# design.net
KiCad netlist of a schematic drawn in EasyEDA Pro
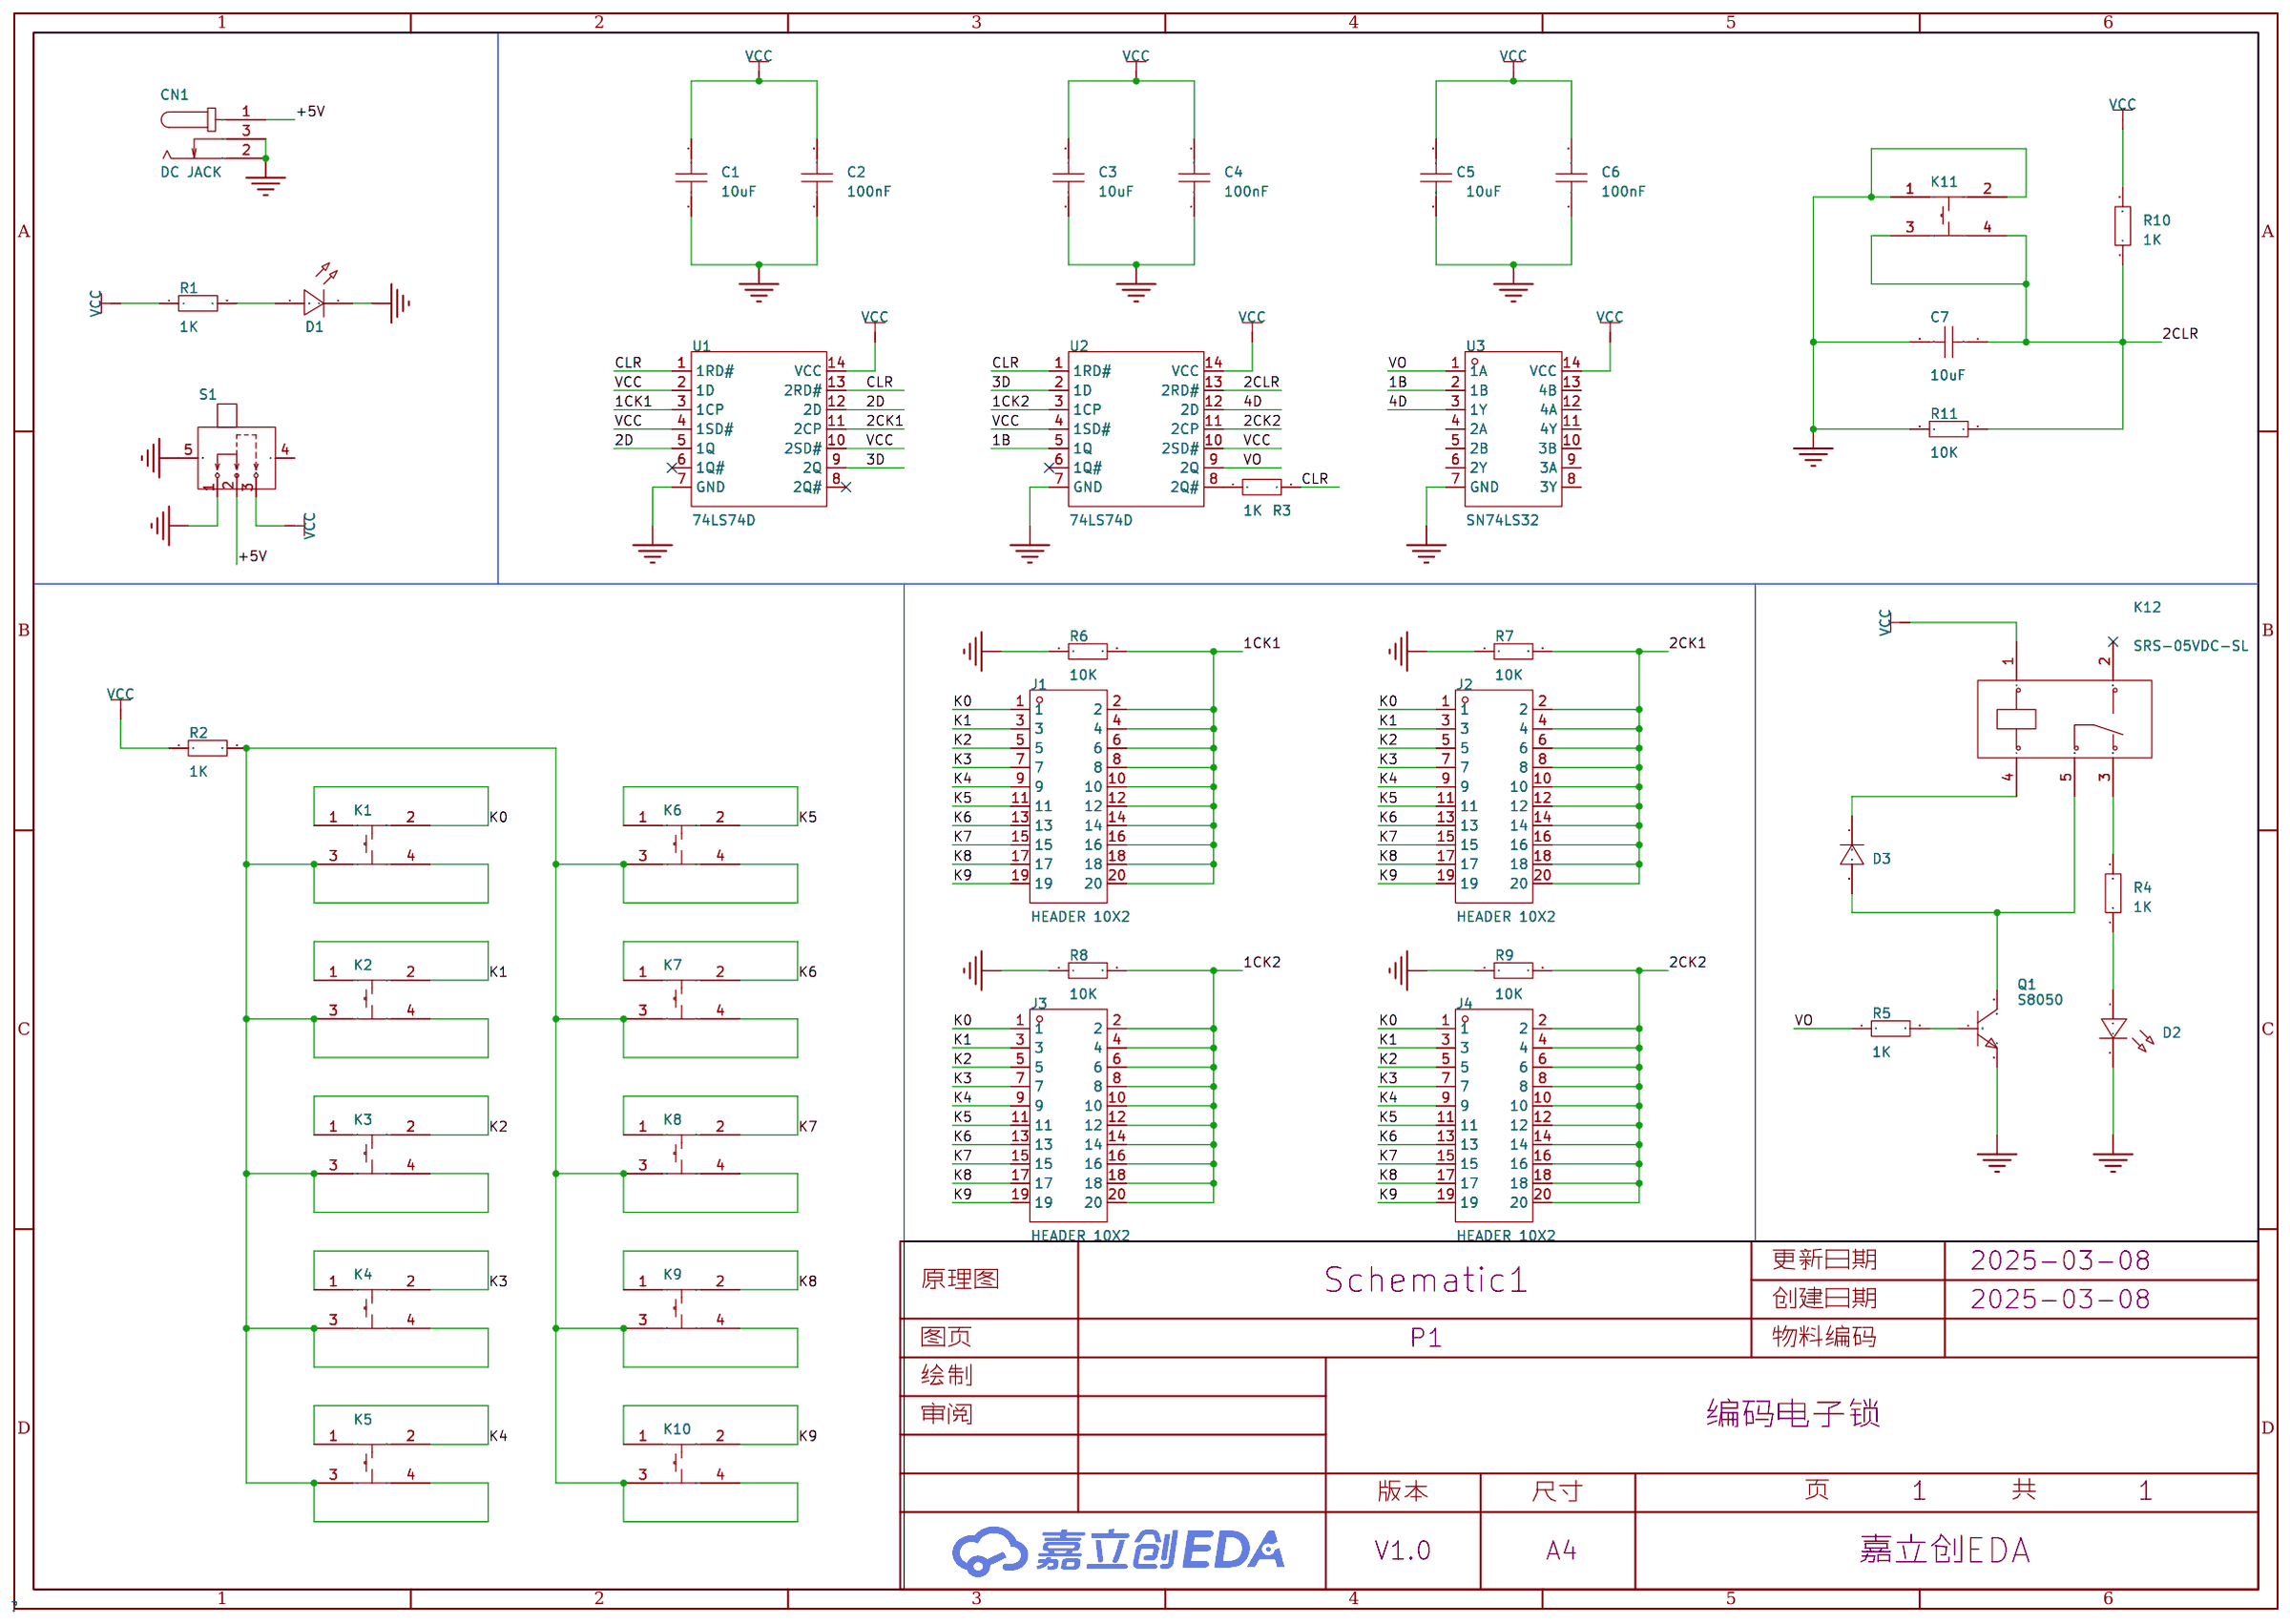
[diagram p0: schematic sheet]

(export (version "E")
  (design (tool "Eeschema 10.0.6"))
  (components
    (comp (ref "C1")
      (value "10uF")
      (footprint "easyedapro:C0805")
      (libsource (lib "easyedapro") (part "CapAcitance"))
    )
    (comp (ref "C2")
      (value "100nF")
      (footprint "easyedapro:C0805")
      (libsource (lib "easyedapro") (part "CapAcitance"))
    )
    (comp (ref "C3")
      (value "10uF")
      (footprint "easyedapro:C0805")
      (libsource (lib "easyedapro") (part "CapAcitance"))
    )
    (comp (ref "C4")
      (value "100nF")
      (footprint "easyedapro:C0805")
      (libsource (lib "easyedapro") (part "CapAcitance"))
    )
    (comp (ref "C5")
      (value "10uF")
      (footprint "easyedapro:C0805")
      (libsource (lib "easyedapro") (part "CapAcitance"))
    )
    (comp (ref "C6")
      (value "100nF")
      (footprint "easyedapro:C0805")
      (libsource (lib "easyedapro") (part "CapAcitance"))
    )
    (comp (ref "C7")
      (value "10uF")
      (footprint "easyedapro:C0805")
      (libsource (lib "easyedapro") (part "CapAcitance"))
    )
    (comp (ref "CN1")
      (value "DC JACK")
      (footprint "easyedapro:DC-IN-TH_DC005")
      (description "连接器类型:DC电源插座;安装方式:弯插;触点内径:2mm;触点外径:6.3mm;额定电流:500mA;额定电压:30V;工作温度范围:-25°C~+70°C;")
      (fields (field (name "Manufacturer") "SHOU HAN(首韩)"))
      (libsource (lib "easyedapro") (part "DC005_C431533"))
    )
    (comp (ref "D1")
      (value "~")
      (footprint "easyedapro:LED_TH-3mm")
      (libsource (lib "easyedapro") (part "LED_TH-R"))
    )
    (comp (ref "D2")
      (value "~")
      (footprint "easyedapro:LED_TH-3mm")
      (libsource (lib "easyedapro") (part "LED_TH-R"))
    )
    (comp (ref "D3")
      (value "LL4148-GS08")
      (footprint "easyedapro:SOD-80_L3.5-W1.5-RD")
      (description "二极管配置:-;正向压降(Vf):860mV@50mA;直流反向耐压(Vr):75V;平均整流电流(Io):300mA;功率:500mW;反向恢复时间(trr):8ns;")
      (fields (field (name "Manufacturer") "VISHAY(威世)"))
      (libsource (lib "easyedapro") (part "LL4148-GS08"))
    )
    (comp (ref "J1")
      (value "HEADER 10X2")
      (footprint "easyedapro:HDR-TH_20P-P2.54-V-M-R2-C10-S2.54")
      (description "插针结构:2x10P;间距:2.54mm;排数:双排;总PIN位数:20P;")
      (fields (field (name "Manufacturer") "ZHOURI(洲日)"))
      (libsource (lib "easyedapro") (part "2.54-2*10"))
    )
    (comp (ref "J2")
      (value "HEADER 10X2")
      (footprint "easyedapro:HDR-TH_20P-P2.54-V-M-R2-C10-S2.54")
      (description "插针结构:2x10P;间距:2.54mm;排数:双排;总PIN位数:20P;")
      (fields (field (name "Manufacturer") "ZHOURI(洲日)"))
      (libsource (lib "easyedapro") (part "2.54-2*10"))
    )
    (comp (ref "J3")
      (value "HEADER 10X2")
      (footprint "easyedapro:HDR-TH_20P-P2.54-V-M-R2-C10-S2.54")
      (description "插针结构:2x10P;间距:2.54mm;排数:双排;总PIN位数:20P;")
      (fields (field (name "Manufacturer") "ZHOURI(洲日)"))
      (libsource (lib "easyedapro") (part "2.54-2*10"))
    )
    (comp (ref "J4")
      (value "HEADER 10X2")
      (footprint "easyedapro:HDR-TH_20P-P2.54-V-M-R2-C10-S2.54")
      (description "插针结构:2x10P;间距:2.54mm;排数:双排;总PIN位数:20P;")
      (fields (field (name "Manufacturer") "ZHOURI(洲日)"))
      (libsource (lib "easyedapro") (part "2.54-2*10"))
    )
    (comp (ref "K1")
      (value "TS-1002S-04526C")
      (footprint "easyedapro:SW-SMD_4P-L6.0-W6.0-P4.50-LS9.0-2")
      (description "电路结构:单刀单掷;按钮形状:圆形按钮;安装方式:立贴;开关长度:6mm;开关宽度:6mm;开关高度:4.5mm;触点电流:50mA;额定电压(DC):12V;带灯:-;机械寿命:-;")
      (fields (field (name "Manufacturer") "XUNPU(讯普)"))
      (libsource (lib "easyedapro") (part "TS-1002S-04526C"))
    )
    (comp (ref "K2")
      (value "TS-1002S-04526C")
      (footprint "easyedapro:SW-SMD_4P-L6.0-W6.0-P4.50-LS9.0-2")
      (description "电路结构:单刀单掷;按钮形状:圆形按钮;安装方式:立贴;开关长度:6mm;开关宽度:6mm;开关高度:4.5mm;触点电流:50mA;额定电压(DC):12V;带灯:-;机械寿命:-;")
      (fields (field (name "Manufacturer") "XUNPU(讯普)"))
      (libsource (lib "easyedapro") (part "TS-1002S-04526C"))
    )
    (comp (ref "K3")
      (value "TS-1002S-04526C")
      (footprint "easyedapro:SW-SMD_4P-L6.0-W6.0-P4.50-LS9.0-2")
      (description "电路结构:单刀单掷;按钮形状:圆形按钮;安装方式:立贴;开关长度:6mm;开关宽度:6mm;开关高度:4.5mm;触点电流:50mA;额定电压(DC):12V;带灯:-;机械寿命:-;")
      (fields (field (name "Manufacturer") "XUNPU(讯普)"))
      (libsource (lib "easyedapro") (part "TS-1002S-04526C"))
    )
    (comp (ref "K4")
      (value "TS-1002S-04526C")
      (footprint "easyedapro:SW-SMD_4P-L6.0-W6.0-P4.50-LS9.0-2")
      (description "电路结构:单刀单掷;按钮形状:圆形按钮;安装方式:立贴;开关长度:6mm;开关宽度:6mm;开关高度:4.5mm;触点电流:50mA;额定电压(DC):12V;带灯:-;机械寿命:-;")
      (fields (field (name "Manufacturer") "XUNPU(讯普)"))
      (libsource (lib "easyedapro") (part "TS-1002S-04526C"))
    )
    (comp (ref "K5")
      (value "TS-1002S-04526C")
      (footprint "easyedapro:SW-SMD_4P-L6.0-W6.0-P4.50-LS9.0-2")
      (description "电路结构:单刀单掷;按钮形状:圆形按钮;安装方式:立贴;开关长度:6mm;开关宽度:6mm;开关高度:4.5mm;触点电流:50mA;额定电压(DC):12V;带灯:-;机械寿命:-;")
      (fields (field (name "Manufacturer") "XUNPU(讯普)"))
      (libsource (lib "easyedapro") (part "TS-1002S-04526C"))
    )
    (comp (ref "K6")
      (value "TS-1002S-04526C")
      (footprint "easyedapro:SW-SMD_4P-L6.0-W6.0-P4.50-LS9.0-2")
      (description "电路结构:单刀单掷;按钮形状:圆形按钮;安装方式:立贴;开关长度:6mm;开关宽度:6mm;开关高度:4.5mm;触点电流:50mA;额定电压(DC):12V;带灯:-;机械寿命:-;")
      (fields (field (name "Manufacturer") "XUNPU(讯普)"))
      (libsource (lib "easyedapro") (part "TS-1002S-04526C"))
    )
    (comp (ref "K7")
      (value "TS-1002S-04526C")
      (footprint "easyedapro:SW-SMD_4P-L6.0-W6.0-P4.50-LS9.0-2")
      (description "电路结构:单刀单掷;按钮形状:圆形按钮;安装方式:立贴;开关长度:6mm;开关宽度:6mm;开关高度:4.5mm;触点电流:50mA;额定电压(DC):12V;带灯:-;机械寿命:-;")
      (fields (field (name "Manufacturer") "XUNPU(讯普)"))
      (libsource (lib "easyedapro") (part "TS-1002S-04526C"))
    )
    (comp (ref "K8")
      (value "TS-1002S-04526C")
      (footprint "easyedapro:SW-SMD_4P-L6.0-W6.0-P4.50-LS9.0-2")
      (description "电路结构:单刀单掷;按钮形状:圆形按钮;安装方式:立贴;开关长度:6mm;开关宽度:6mm;开关高度:4.5mm;触点电流:50mA;额定电压(DC):12V;带灯:-;机械寿命:-;")
      (fields (field (name "Manufacturer") "XUNPU(讯普)"))
      (libsource (lib "easyedapro") (part "TS-1002S-04526C"))
    )
    (comp (ref "K9")
      (value "TS-1002S-04526C")
      (footprint "easyedapro:SW-SMD_4P-L6.0-W6.0-P4.50-LS9.0-2")
      (description "电路结构:单刀单掷;按钮形状:圆形按钮;安装方式:立贴;开关长度:6mm;开关宽度:6mm;开关高度:4.5mm;触点电流:50mA;额定电压(DC):12V;带灯:-;机械寿命:-;")
      (fields (field (name "Manufacturer") "XUNPU(讯普)"))
      (libsource (lib "easyedapro") (part "TS-1002S-04526C"))
    )
    (comp (ref "K10")
      (value "TS-1002S-04526C")
      (footprint "easyedapro:SW-SMD_4P-L6.0-W6.0-P4.50-LS9.0-2")
      (description "电路结构:单刀单掷;按钮形状:圆形按钮;安装方式:立贴;开关长度:6mm;开关宽度:6mm;开关高度:4.5mm;触点电流:50mA;额定电压(DC):12V;带灯:-;机械寿命:-;")
      (fields (field (name "Manufacturer") "XUNPU(讯普)"))
      (libsource (lib "easyedapro") (part "TS-1002S-04526C"))
    )
    (comp (ref "K11")
      (value "TS-1002S-04526C")
      (footprint "easyedapro:SW-SMD_4P-L6.0-W6.0-P4.50-LS9.0-2")
      (description "电路结构:单刀单掷;按钮形状:圆形按钮;安装方式:立贴;开关长度:6mm;开关宽度:6mm;开关高度:4.5mm;触点电流:50mA;额定电压(DC):12V;带灯:-;机械寿命:-;")
      (fields (field (name "Manufacturer") "XUNPU(讯普)"))
      (libsource (lib "easyedapro") (part "TS-1002S-04526C"))
    )
    (comp (ref "K12")
      (value "SRS-05VDC-SL")
      (footprint "easyedapro:RELAY-TH_SRD-XXVDC-XL-C")
      (description "线圈电压:5V;触点形式:一组转换:1C(单刀双掷-转换);触点容量(电阻负载):-;最大切换电压:250V@AC;最大切换电流:15A;")
      (fields (field (name "Manufacturer") "松乐"))
      (libsource (lib "easyedapro") (part "SRD-05VDC-SL-C"))
    )
    (comp (ref "Q1")
      (value "S8050")
      (footprint "easyedapro:SOT-23-3_L3.0-W1.7-P0.95-LS2.9-BR")
      (description "晶体管类型:NPN;集电极电流(Ic):500mA;集射极击穿电压(Vceo):25V;耗散功率(Pd):300mW;直流电流增益(hFE):120@500mA,1V;")
      (fields (field (name "Manufacturer") "MDD(辰达半导体)"))
      (libsource (lib "easyedapro") (part "S8050-J3Y"))
    )
    (comp (ref "R1") (value "1K") (footprint "easyedapro:R0805") (libsource (lib "easyedapro") (part "电阻")))
    (comp (ref "R2") (value "1K") (footprint "easyedapro:R0805") (libsource (lib "easyedapro") (part "电阻")))
    (comp (ref "R3") (value "1K") (footprint "easyedapro:R0805") (libsource (lib "easyedapro") (part "电阻")))
    (comp (ref "R4") (value "1K") (footprint "easyedapro:R0805") (libsource (lib "easyedapro") (part "电阻")))
    (comp (ref "R5") (value "1K") (footprint "easyedapro:R0805") (libsource (lib "easyedapro") (part "电阻")))
    (comp (ref "R6") (value "10K") (footprint "easyedapro:R0805") (libsource (lib "easyedapro") (part "电阻")))
    (comp (ref "R7") (value "10K") (footprint "easyedapro:R0805") (libsource (lib "easyedapro") (part "电阻")))
    (comp (ref "R8") (value "10K") (footprint "easyedapro:R0805") (libsource (lib "easyedapro") (part "电阻")))
    (comp (ref "R9") (value "10K") (footprint "easyedapro:R0805") (libsource (lib "easyedapro") (part "电阻")))
    (comp (ref "R10") (value "1K") (footprint "easyedapro:R0805") (libsource (lib "easyedapro") (part "电阻")))
    (comp (ref "R11") (value "10K") (footprint "easyedapro:R0805") (libsource (lib "easyedapro") (part "电阻")))
    (comp (ref "S1")
      (value "SS12F44G5")
      (footprint "easyedapro:SW-TH_SHOU-HAN_SS12F44G4")
      (description "拨动开关 立式直脚插件 二档 柄高5mm")
      (fields (field (name "Manufacturer") "HanElectricity(瀚源)"))
      (libsource (lib "easyedapro") (part "SS12F44G5"))
    )
    (comp (ref "U1")
      (value "74LS74D")
      (footprint "easyedapro:DIP-14_L19.1-W6.4-P2.54-LS7.6-BL")
      (description "类型:D-型;工作电压:2V~6V;时钟频率(fc):82MHz;元件数:2;每个元件位数:1;静态电流(Iq):40uA;")
      (fields (field (name "Manufacturer") "LX(灵星芯微)"))
      (libsource (lib "easyedapro") (part "SN74LS74N"))
    )
    (comp (ref "U2")
      (value "74LS74D")
      (footprint "easyedapro:DIP-14_L19.1-W6.4-P2.54-LS7.6-BL")
      (description "类型:D-型;工作电压:2V~6V;时钟频率(fc):82MHz;元件数:2;每个元件位数:1;静态电流(Iq):40uA;")
      (fields (field (name "Manufacturer") "LX(灵星芯微)"))
      (libsource (lib "easyedapro") (part "SN74LS74N"))
    )
    (comp (ref "U3")
      (value "SN74LS32")
      (footprint "easyedapro:PDIP-14_L19.6-W6.5-P2.54-LS7.9-BL")
      (description "逻辑类型:或门;通道数:4;电源电压:4.75V~5.25V;最大传播延迟:22ns@5V,15pF;")
      (fields (field (name "Manufacturer") "TI(德州仪器)"))
      (libsource (lib "easyedapro") (part "SN74LS32N"))
    )
  )
  (nets
    (net (code "1") (name "/+5V") (class "Default")
      (node (ref "CN1") (pin "1") (pinfunction "1_1") (pintype "unspecified"))
      (node (ref "S1") (pin "2") (pinfunction "2_2") (pintype "unspecified"))
    )
    (net (code "2") (name "/1B") (class "Default")
      (node (ref "U2") (pin "5") (pinfunction "1Q_5") (pintype "unspecified"))
      (node (ref "U3") (pin "2") (pinfunction "1B_2") (pintype "unspecified"))
    )
    (net (code "3") (name "/1CK1") (class "Default")
      (node (ref "J1") (pin "10") (pinfunction "10_10") (pintype "unspecified"))
      (node (ref "J1") (pin "12") (pinfunction "12_12") (pintype "unspecified"))
      (node (ref "J1") (pin "14") (pinfunction "14_14") (pintype "unspecified"))
      (node (ref "J1") (pin "16") (pinfunction "16_16") (pintype "unspecified"))
      (node (ref "J1") (pin "18") (pinfunction "18_18") (pintype "unspecified"))
      (node (ref "J1") (pin "2") (pinfunction "2_2") (pintype "unspecified"))
      (node (ref "J1") (pin "20") (pinfunction "20_20") (pintype "unspecified"))
      (node (ref "J1") (pin "4") (pinfunction "4_4") (pintype "unspecified"))
      (node (ref "J1") (pin "6") (pinfunction "6_6") (pintype "unspecified"))
      (node (ref "J1") (pin "8") (pinfunction "8_8") (pintype "unspecified"))
      (node (ref "R6") (pin "2") (pinfunction "2_2") (pintype "input"))
      (node (ref "U1") (pin "3") (pinfunction "1CP_3") (pintype "unspecified"))
    )
    (net (code "4") (name "/1CK2") (class "Default")
      (node (ref "J3") (pin "10") (pinfunction "10_10") (pintype "unspecified"))
      (node (ref "J3") (pin "12") (pinfunction "12_12") (pintype "unspecified"))
      (node (ref "J3") (pin "14") (pinfunction "14_14") (pintype "unspecified"))
      (node (ref "J3") (pin "16") (pinfunction "16_16") (pintype "unspecified"))
      (node (ref "J3") (pin "18") (pinfunction "18_18") (pintype "unspecified"))
      (node (ref "J3") (pin "2") (pinfunction "2_2") (pintype "unspecified"))
      (node (ref "J3") (pin "20") (pinfunction "20_20") (pintype "unspecified"))
      (node (ref "J3") (pin "4") (pinfunction "4_4") (pintype "unspecified"))
      (node (ref "J3") (pin "6") (pinfunction "6_6") (pintype "unspecified"))
      (node (ref "J3") (pin "8") (pinfunction "8_8") (pintype "unspecified"))
      (node (ref "R8") (pin "2") (pinfunction "2_2") (pintype "input"))
      (node (ref "U2") (pin "3") (pinfunction "1CP_3") (pintype "unspecified"))
    )
    (net (code "5") (name "/2CK1") (class "Default")
      (node (ref "J2") (pin "10") (pinfunction "10_10") (pintype "unspecified"))
      (node (ref "J2") (pin "12") (pinfunction "12_12") (pintype "unspecified"))
      (node (ref "J2") (pin "14") (pinfunction "14_14") (pintype "unspecified"))
      (node (ref "J2") (pin "16") (pinfunction "16_16") (pintype "unspecified"))
      (node (ref "J2") (pin "18") (pinfunction "18_18") (pintype "unspecified"))
      (node (ref "J2") (pin "2") (pinfunction "2_2") (pintype "unspecified"))
      (node (ref "J2") (pin "20") (pinfunction "20_20") (pintype "unspecified"))
      (node (ref "J2") (pin "4") (pinfunction "4_4") (pintype "unspecified"))
      (node (ref "J2") (pin "6") (pinfunction "6_6") (pintype "unspecified"))
      (node (ref "J2") (pin "8") (pinfunction "8_8") (pintype "unspecified"))
      (node (ref "R7") (pin "2") (pinfunction "2_2") (pintype "input"))
      (node (ref "U1") (pin "11") (pinfunction "2CP_11") (pintype "unspecified"))
    )
    (net (code "6") (name "/2CK2") (class "Default")
      (node (ref "J4") (pin "10") (pinfunction "10_10") (pintype "unspecified"))
      (node (ref "J4") (pin "12") (pinfunction "12_12") (pintype "unspecified"))
      (node (ref "J4") (pin "14") (pinfunction "14_14") (pintype "unspecified"))
      (node (ref "J4") (pin "16") (pinfunction "16_16") (pintype "unspecified"))
      (node (ref "J4") (pin "18") (pinfunction "18_18") (pintype "unspecified"))
      (node (ref "J4") (pin "2") (pinfunction "2_2") (pintype "unspecified"))
      (node (ref "J4") (pin "20") (pinfunction "20_20") (pintype "unspecified"))
      (node (ref "J4") (pin "4") (pinfunction "4_4") (pintype "unspecified"))
      (node (ref "J4") (pin "6") (pinfunction "6_6") (pintype "unspecified"))
      (node (ref "J4") (pin "8") (pinfunction "8_8") (pintype "unspecified"))
      (node (ref "R9") (pin "2") (pinfunction "2_2") (pintype "input"))
      (node (ref "U2") (pin "11") (pinfunction "2CP_11") (pintype "unspecified"))
    )
    (net (code "7") (name "/2CLR") (class "Default")
      (node (ref "C7") (pin "1") (pinfunction "1_1") (pintype "input"))
      (node (ref "K11") (pin "3") (pinfunction "3_3") (pintype "unspecified"))
      (node (ref "K11") (pin "4") (pinfunction "4_4") (pintype "unspecified"))
      (node (ref "R10") (pin "1") (pinfunction "1_1") (pintype "input"))
      (node (ref "R11") (pin "1") (pinfunction "1_1") (pintype "input"))
      (node (ref "U2") (pin "13") (pinfunction "2RD#_13") (pintype "unspecified"))
    )
    (net (code "8") (name "/2D") (class "Default")
      (node (ref "U1") (pin "12") (pinfunction "2D_12") (pintype "unspecified"))
      (node (ref "U1") (pin "5") (pinfunction "1Q_5") (pintype "unspecified"))
    )
    (net (code "9") (name "/3D") (class "Default")
      (node (ref "U1") (pin "9") (pinfunction "2Q_9") (pintype "unspecified"))
      (node (ref "U2") (pin "2") (pinfunction "1D_2") (pintype "unspecified"))
    )
    (net (code "10") (name "/4D") (class "Default")
      (node (ref "U2") (pin "12") (pinfunction "2D_12") (pintype "unspecified"))
      (node (ref "U3") (pin "3") (pinfunction "1Y_3") (pintype "unspecified"))
    )
    (net (code "11") (name "/CLR") (class "Default")
      (node (ref "R3") (pin "2") (pinfunction "2_2") (pintype "input"))
      (node (ref "U1") (pin "1") (pinfunction "1RD#_1") (pintype "unspecified"))
      (node (ref "U1") (pin "13") (pinfunction "2RD#_13") (pintype "unspecified"))
      (node (ref "U2") (pin "1") (pinfunction "1RD#_1") (pintype "unspecified"))
    )
    (net (code "12") (name "/K0") (class "Default")
      (node (ref "J1") (pin "1") (pinfunction "1_1") (pintype "unspecified"))
      (node (ref "J2") (pin "1") (pinfunction "1_1") (pintype "unspecified"))
      (node (ref "J3") (pin "1") (pinfunction "1_1") (pintype "unspecified"))
      (node (ref "J4") (pin "1") (pinfunction "1_1") (pintype "unspecified"))
      (node (ref "K1") (pin "1") (pinfunction "1_1") (pintype "unspecified"))
      (node (ref "K1") (pin "2") (pinfunction "2_2") (pintype "unspecified"))
    )
    (net (code "13") (name "/K1") (class "Default")
      (node (ref "J1") (pin "3") (pinfunction "3_3") (pintype "unspecified"))
      (node (ref "J2") (pin "3") (pinfunction "3_3") (pintype "unspecified"))
      (node (ref "J3") (pin "3") (pinfunction "3_3") (pintype "unspecified"))
      (node (ref "J4") (pin "3") (pinfunction "3_3") (pintype "unspecified"))
      (node (ref "K2") (pin "1") (pinfunction "1_1") (pintype "unspecified"))
      (node (ref "K2") (pin "2") (pinfunction "2_2") (pintype "unspecified"))
    )
    (net (code "14") (name "/K2") (class "Default")
      (node (ref "J1") (pin "5") (pinfunction "5_5") (pintype "unspecified"))
      (node (ref "J2") (pin "5") (pinfunction "5_5") (pintype "unspecified"))
      (node (ref "J3") (pin "5") (pinfunction "5_5") (pintype "unspecified"))
      (node (ref "J4") (pin "5") (pinfunction "5_5") (pintype "unspecified"))
      (node (ref "K3") (pin "1") (pinfunction "1_1") (pintype "unspecified"))
      (node (ref "K3") (pin "2") (pinfunction "2_2") (pintype "unspecified"))
    )
    (net (code "15") (name "/K3") (class "Default")
      (node (ref "J1") (pin "7") (pinfunction "7_7") (pintype "unspecified"))
      (node (ref "J2") (pin "7") (pinfunction "7_7") (pintype "unspecified"))
      (node (ref "J3") (pin "7") (pinfunction "7_7") (pintype "unspecified"))
      (node (ref "J4") (pin "7") (pinfunction "7_7") (pintype "unspecified"))
      (node (ref "K4") (pin "1") (pinfunction "1_1") (pintype "unspecified"))
      (node (ref "K4") (pin "2") (pinfunction "2_2") (pintype "unspecified"))
    )
    (net (code "16") (name "/K4") (class "Default")
      (node (ref "J1") (pin "9") (pinfunction "9_9") (pintype "unspecified"))
      (node (ref "J2") (pin "9") (pinfunction "9_9") (pintype "unspecified"))
      (node (ref "J3") (pin "9") (pinfunction "9_9") (pintype "unspecified"))
      (node (ref "J4") (pin "9") (pinfunction "9_9") (pintype "unspecified"))
      (node (ref "K5") (pin "1") (pinfunction "1_1") (pintype "unspecified"))
      (node (ref "K5") (pin "2") (pinfunction "2_2") (pintype "unspecified"))
    )
    (net (code "17") (name "/K5") (class "Default")
      (node (ref "J1") (pin "11") (pinfunction "11_11") (pintype "unspecified"))
      (node (ref "J2") (pin "11") (pinfunction "11_11") (pintype "unspecified"))
      (node (ref "J3") (pin "11") (pinfunction "11_11") (pintype "unspecified"))
      (node (ref "J4") (pin "11") (pinfunction "11_11") (pintype "unspecified"))
      (node (ref "K6") (pin "1") (pinfunction "1_1") (pintype "unspecified"))
      (node (ref "K6") (pin "2") (pinfunction "2_2") (pintype "unspecified"))
    )
    (net (code "18") (name "/K6") (class "Default")
      (node (ref "J1") (pin "13") (pinfunction "13_13") (pintype "unspecified"))
      (node (ref "J2") (pin "13") (pinfunction "13_13") (pintype "unspecified"))
      (node (ref "J3") (pin "13") (pinfunction "13_13") (pintype "unspecified"))
      (node (ref "J4") (pin "13") (pinfunction "13_13") (pintype "unspecified"))
      (node (ref "K7") (pin "1") (pinfunction "1_1") (pintype "unspecified"))
      (node (ref "K7") (pin "2") (pinfunction "2_2") (pintype "unspecified"))
    )
    (net (code "19") (name "/K7") (class "Default")
      (node (ref "J1") (pin "15") (pinfunction "15_15") (pintype "unspecified"))
      (node (ref "J2") (pin "15") (pinfunction "15_15") (pintype "unspecified"))
      (node (ref "J3") (pin "15") (pinfunction "15_15") (pintype "unspecified"))
      (node (ref "J4") (pin "15") (pinfunction "15_15") (pintype "unspecified"))
      (node (ref "K8") (pin "1") (pinfunction "1_1") (pintype "unspecified"))
      (node (ref "K8") (pin "2") (pinfunction "2_2") (pintype "unspecified"))
    )
    (net (code "20") (name "/K8") (class "Default")
      (node (ref "J1") (pin "17") (pinfunction "17_17") (pintype "unspecified"))
      (node (ref "J2") (pin "17") (pinfunction "17_17") (pintype "unspecified"))
      (node (ref "J3") (pin "17") (pinfunction "17_17") (pintype "unspecified"))
      (node (ref "J4") (pin "17") (pinfunction "17_17") (pintype "unspecified"))
      (node (ref "K9") (pin "1") (pinfunction "1_1") (pintype "unspecified"))
      (node (ref "K9") (pin "2") (pinfunction "2_2") (pintype "unspecified"))
    )
    (net (code "21") (name "/K9") (class "Default")
      (node (ref "J1") (pin "19") (pinfunction "19_19") (pintype "unspecified"))
      (node (ref "J2") (pin "19") (pinfunction "19_19") (pintype "unspecified"))
      (node (ref "J3") (pin "19") (pinfunction "19_19") (pintype "unspecified"))
      (node (ref "J4") (pin "19") (pinfunction "19_19") (pintype "unspecified"))
      (node (ref "K10") (pin "1") (pinfunction "1_1") (pintype "unspecified"))
      (node (ref "K10") (pin "2") (pinfunction "2_2") (pintype "unspecified"))
    )
    (net (code "22") (name "/VO") (class "Default")
      (node (ref "R5") (pin "1") (pinfunction "1_1") (pintype "input"))
      (node (ref "U2") (pin "9") (pinfunction "2Q_9") (pintype "unspecified"))
      (node (ref "U3") (pin "1") (pinfunction "1A_1") (pintype "unspecified"))
    )
    (net (code "23") (name "GND") (class "Default")
      (node (ref "C1") (pin "1") (pinfunction "1_1") (pintype "input"))
      (node (ref "C2") (pin "1") (pinfunction "1_1") (pintype "input"))
      (node (ref "C3") (pin "1") (pinfunction "1_1") (pintype "input"))
      (node (ref "C4") (pin "1") (pinfunction "1_1") (pintype "input"))
      (node (ref "C5") (pin "1") (pinfunction "1_1") (pintype "input"))
      (node (ref "C6") (pin "1") (pinfunction "1_1") (pintype "input"))
      (node (ref "C7") (pin "2") (pinfunction "2_2") (pintype "input"))
      (node (ref "CN1") (pin "2") (pinfunction "2_2") (pintype "unspecified"))
      (node (ref "CN1") (pin "3") (pinfunction "3_3") (pintype "unspecified"))
      (node (ref "D1") (pin "2") (pinfunction "A_2") (pintype "input"))
      (node (ref "D2") (pin "2") (pinfunction "A_2") (pintype "input"))
      (node (ref "K11") (pin "1") (pinfunction "1_1") (pintype "unspecified"))
      (node (ref "K11") (pin "2") (pinfunction "2_2") (pintype "unspecified"))
      (node (ref "Q1") (pin "2") (pinfunction "E_2") (pintype "unspecified"))
      (node (ref "R11") (pin "2") (pinfunction "2_2") (pintype "input"))
      (node (ref "R6") (pin "1") (pinfunction "1_1") (pintype "input"))
      (node (ref "R7") (pin "1") (pinfunction "1_1") (pintype "input"))
      (node (ref "R8") (pin "1") (pinfunction "1_1") (pintype "input"))
      (node (ref "R9") (pin "1") (pinfunction "1_1") (pintype "input"))
      (node (ref "S1") (pin "1") (pinfunction "1_1") (pintype "unspecified"))
      (node (ref "S1") (pin "5") (pinfunction "5_5") (pintype "unspecified"))
      (node (ref "U1") (pin "7") (pinfunction "GND_7") (pintype "unspecified"))
      (node (ref "U2") (pin "7") (pinfunction "GND_7") (pintype "unspecified"))
      (node (ref "U3") (pin "7") (pinfunction "GND_7") (pintype "unspecified"))
    )
    (net (code "24") (name "Net-(D1-C)") (class "Default")
      (node (ref "D1") (pin "1") (pinfunction "C_1") (pintype "input"))
      (node (ref "R1") (pin "2") (pinfunction "2_2") (pintype "input"))
    )
    (net (code "25") (name "Net-(D2-C)") (class "Default")
      (node (ref "D2") (pin "1") (pinfunction "C_1") (pintype "input"))
      (node (ref "R4") (pin "1") (pinfunction "1_1") (pintype "input"))
    )
    (net (code "26") (name "Net-(D3-A)") (class "Default")
      (node (ref "D3") (pin "2") (pinfunction "A_2") (pintype "unspecified"))
      (node (ref "K12") (pin "5") (pinfunction "5_5") (pintype "input"))
      (node (ref "Q1") (pin "3") (pinfunction "C_3") (pintype "unspecified"))
    )
    (net (code "27") (name "Net-(D3-C)") (class "Default")
      (node (ref "D3") (pin "1") (pinfunction "C_1") (pintype "unspecified"))
      (node (ref "K12") (pin "4") (pinfunction "4_4") (pintype "input"))
    )
    (net (code "28") (name "Net-(K1-Pad3)") (class "Default")
      (node (ref "K1") (pin "3") (pinfunction "3_3") (pintype "unspecified"))
      (node (ref "K1") (pin "4") (pinfunction "4_4") (pintype "unspecified"))
      (node (ref "K10") (pin "3") (pinfunction "3_3") (pintype "unspecified"))
      (node (ref "K10") (pin "4") (pinfunction "4_4") (pintype "unspecified"))
      (node (ref "K2") (pin "3") (pinfunction "3_3") (pintype "unspecified"))
      (node (ref "K2") (pin "4") (pinfunction "4_4") (pintype "unspecified"))
      (node (ref "K3") (pin "3") (pinfunction "3_3") (pintype "unspecified"))
      (node (ref "K3") (pin "4") (pinfunction "4_4") (pintype "unspecified"))
      (node (ref "K4") (pin "3") (pinfunction "3_3") (pintype "unspecified"))
      (node (ref "K4") (pin "4") (pinfunction "4_4") (pintype "unspecified"))
      (node (ref "K5") (pin "3") (pinfunction "3_3") (pintype "unspecified"))
      (node (ref "K5") (pin "4") (pinfunction "4_4") (pintype "unspecified"))
      (node (ref "K6") (pin "3") (pinfunction "3_3") (pintype "unspecified"))
      (node (ref "K6") (pin "4") (pinfunction "4_4") (pintype "unspecified"))
      (node (ref "K7") (pin "3") (pinfunction "3_3") (pintype "unspecified"))
      (node (ref "K7") (pin "4") (pinfunction "4_4") (pintype "unspecified"))
      (node (ref "K8") (pin "3") (pinfunction "3_3") (pintype "unspecified"))
      (node (ref "K8") (pin "4") (pinfunction "4_4") (pintype "unspecified"))
      (node (ref "K9") (pin "3") (pinfunction "3_3") (pintype "unspecified"))
      (node (ref "K9") (pin "4") (pinfunction "4_4") (pintype "unspecified"))
      (node (ref "R2") (pin "2") (pinfunction "2_2") (pintype "input"))
    )
    (net (code "29") (name "Net-(K12-Pad3)") (class "Default")
      (node (ref "K12") (pin "3") (pinfunction "3_3") (pintype "input"))
      (node (ref "R4") (pin "2") (pinfunction "2_2") (pintype "input"))
    )
    (net (code "30") (name "Net-(Q1-B)") (class "Default")
      (node (ref "Q1") (pin "1") (pinfunction "B_1") (pintype "unspecified"))
      (node (ref "R5") (pin "2") (pinfunction "2_2") (pintype "input"))
    )
    (net (code "31") (name "Net-(U2-2Q#)") (class "Default")
      (node (ref "R3") (pin "1") (pinfunction "1_1") (pintype "input"))
      (node (ref "U2") (pin "8") (pinfunction "2Q#_8") (pintype "unspecified"))
    )
    (net (code "32") (name "VCC") (class "Default")
      (node (ref "C1") (pin "2") (pinfunction "2_2") (pintype "input"))
      (node (ref "C2") (pin "2") (pinfunction "2_2") (pintype "input"))
      (node (ref "C3") (pin "2") (pinfunction "2_2") (pintype "input"))
      (node (ref "C4") (pin "2") (pinfunction "2_2") (pintype "input"))
      (node (ref "C5") (pin "2") (pinfunction "2_2") (pintype "input"))
      (node (ref "C6") (pin "2") (pinfunction "2_2") (pintype "input"))
      (node (ref "K12") (pin "1") (pinfunction "1_1") (pintype "input"))
      (node (ref "R1") (pin "1") (pinfunction "1_1") (pintype "input"))
      (node (ref "R10") (pin "2") (pinfunction "2_2") (pintype "input"))
      (node (ref "R2") (pin "1") (pinfunction "1_1") (pintype "input"))
      (node (ref "S1") (pin "3") (pinfunction "3_3") (pintype "unspecified"))
      (node (ref "U1") (pin "10") (pinfunction "2SD#_10") (pintype "unspecified"))
      (node (ref "U1") (pin "14") (pinfunction "VCC_14") (pintype "unspecified"))
      (node (ref "U1") (pin "2") (pinfunction "1D_2") (pintype "unspecified"))
      (node (ref "U1") (pin "4") (pinfunction "1SD#_4") (pintype "unspecified"))
      (node (ref "U2") (pin "10") (pinfunction "2SD#_10") (pintype "unspecified"))
      (node (ref "U2") (pin "14") (pinfunction "VCC_14") (pintype "unspecified"))
      (node (ref "U2") (pin "4") (pinfunction "1SD#_4") (pintype "unspecified"))
      (node (ref "U3") (pin "14") (pinfunction "VCC_14") (pintype "unspecified"))
    )
    (net (code "33") (name "unconnected-(K12-Pad2)") (class "Default")
      (node (ref "K12") (pin "2") (pinfunction "2_2") (pintype "input+no_connect"))
    )
    (net (code "34") (name "unconnected-(S1-Pad4)") (class "Default")
      (node (ref "S1") (pin "4") (pinfunction "4_4") (pintype "unspecified"))
    )
    (net (code "35") (name "unconnected-(U1-1Q#-Pad6)") (class "Default")
      (node (ref "U1") (pin "6") (pinfunction "1Q#_6") (pintype "unspecified+no_connect"))
    )
    (net (code "36") (name "unconnected-(U1-2Q#-Pad8)") (class "Default")
      (node (ref "U1") (pin "8") (pinfunction "2Q#_8") (pintype "unspecified+no_connect"))
    )
    (net (code "37") (name "unconnected-(U2-1Q#-Pad6)") (class "Default")
      (node (ref "U2") (pin "6") (pinfunction "1Q#_6") (pintype "unspecified+no_connect"))
    )
    (net (code "38") (name "unconnected-(U3-2A-Pad4)") (class "Default")
      (node (ref "U3") (pin "4") (pinfunction "2A_4") (pintype "unspecified"))
    )
    (net (code "39") (name "unconnected-(U3-2B-Pad5)") (class "Default")
      (node (ref "U3") (pin "5") (pinfunction "2B_5") (pintype "unspecified"))
    )
    (net (code "40") (name "unconnected-(U3-2Y-Pad6)") (class "Default")
      (node (ref "U3") (pin "6") (pinfunction "2Y_6") (pintype "unspecified"))
    )
    (net (code "41") (name "unconnected-(U3-3A-Pad9)") (class "Default")
      (node (ref "U3") (pin "9") (pinfunction "3A_9") (pintype "unspecified"))
    )
    (net (code "42") (name "unconnected-(U3-3B-Pad10)") (class "Default")
      (node (ref "U3") (pin "10") (pinfunction "3B_10") (pintype "unspecified"))
    )
    (net (code "43") (name "unconnected-(U3-3Y-Pad8)") (class "Default")
      (node (ref "U3") (pin "8") (pinfunction "3Y_8") (pintype "unspecified"))
    )
    (net (code "44") (name "unconnected-(U3-4A-Pad12)") (class "Default")
      (node (ref "U3") (pin "12") (pinfunction "4A_12") (pintype "unspecified"))
    )
    (net (code "45") (name "unconnected-(U3-4B-Pad13)") (class "Default")
      (node (ref "U3") (pin "13") (pinfunction "4B_13") (pintype "unspecified"))
    )
    (net (code "46") (name "unconnected-(U3-4Y-Pad11)") (class "Default")
      (node (ref "U3") (pin "11") (pinfunction "4Y_11") (pintype "unspecified"))
    )
  )
)
